# MCU.net
KiCad netlist of a schematic drawn in Altium Designer
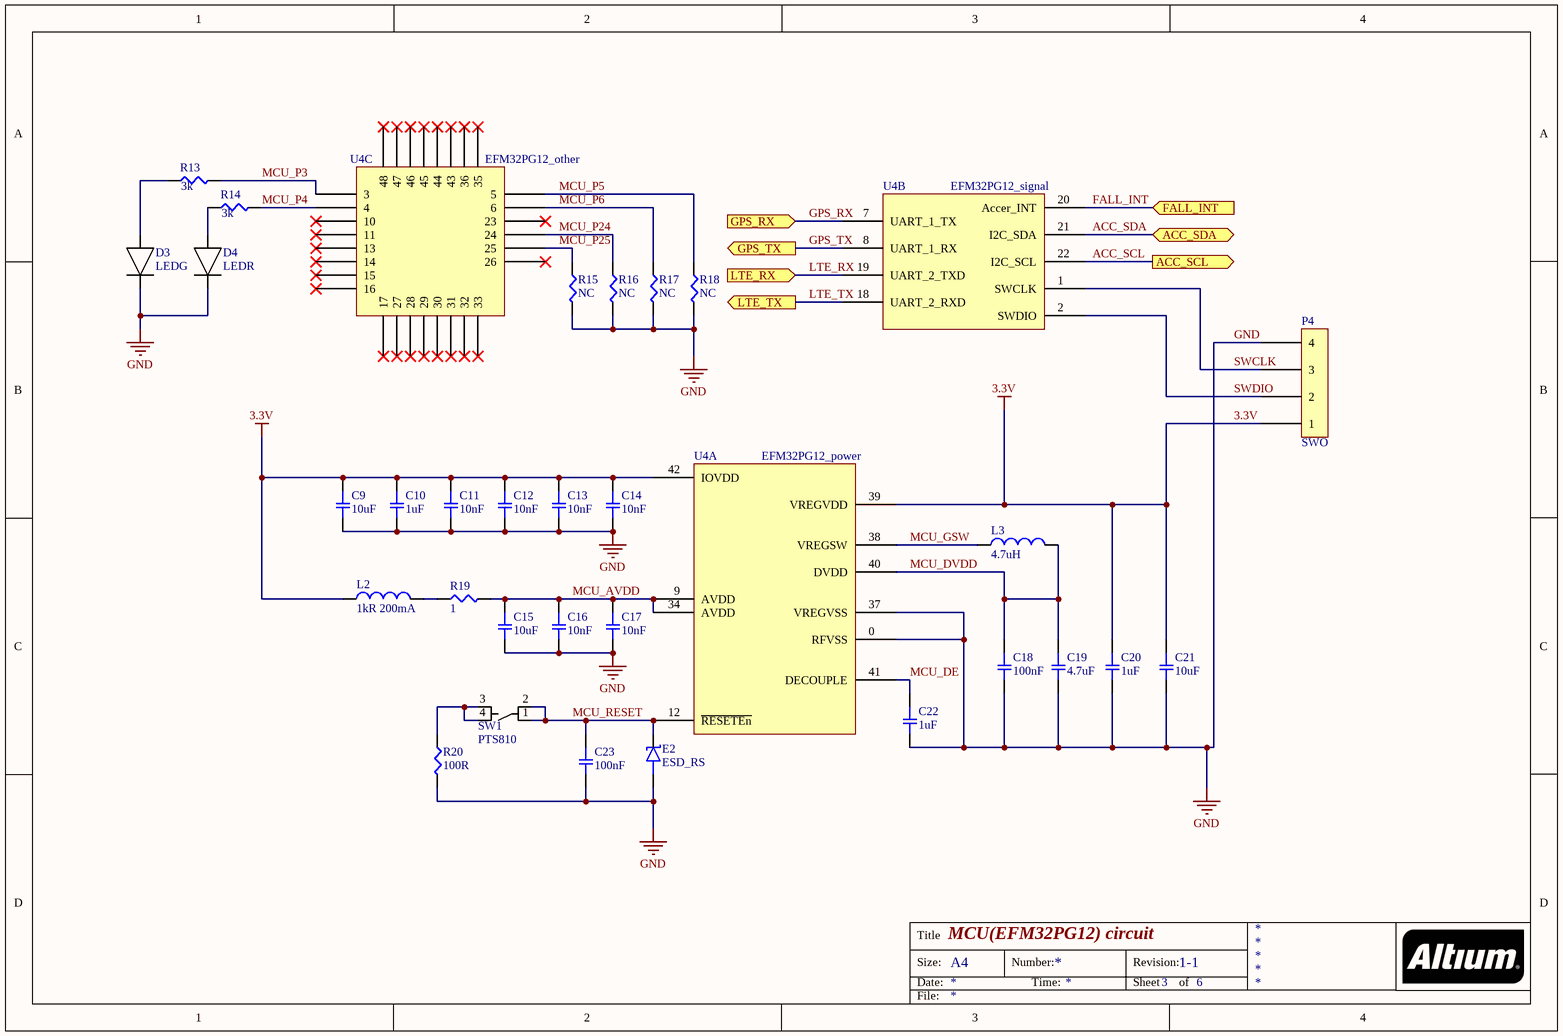
[diagram p0: MCU.SchDoc]

(export (version "E")
  (design (tool "Eeschema 10.0.6"))
  (components
    (comp (ref "C9")
      (value "10uF")
      (footprint "0603-CAP")
      (fields (field (name "Comment") "0603C 10UF"))
      (libsource (lib "passive components") (part "0603C 10UF"))
    )
    (comp (ref "C10")
      (value "1uF")
      (footprint "0603-CAP")
      (fields (field (name "Comment") "0603C 1UF"))
      (libsource (lib "passive components") (part "0603C 1UF"))
    )
    (comp (ref "C11")
      (value "10nF")
      (footprint "0603-CAP")
      (fields (field (name "Comment") "0603C 10NF"))
      (libsource (lib "passive components") (part "0603C 10NF"))
    )
    (comp (ref "C12")
      (value "10nF")
      (footprint "0603-CAP")
      (fields (field (name "Comment") "0603C 10NF"))
      (libsource (lib "passive components") (part "0603C 10NF"))
    )
    (comp (ref "C13")
      (value "10nF")
      (footprint "0603-CAP")
      (fields (field (name "Comment") "0603C 10NF"))
      (libsource (lib "passive components") (part "0603C 10NF"))
    )
    (comp (ref "C14")
      (value "10nF")
      (footprint "0603-CAP")
      (fields (field (name "Comment") "0603C 10NF"))
      (libsource (lib "passive components") (part "0603C 10NF"))
    )
    (comp (ref "C15")
      (value "10uF")
      (footprint "0603-CAP")
      (fields (field (name "Comment") "0603C 10UF"))
      (libsource (lib "passive components") (part "0603C 10UF"))
    )
    (comp (ref "C16")
      (value "10nF")
      (footprint "0603-CAP")
      (fields (field (name "Comment") "0603C 10NF"))
      (libsource (lib "passive components") (part "0603C 10NF"))
    )
    (comp (ref "C17")
      (value "10nF")
      (footprint "0603-CAP")
      (fields (field (name "Comment") "0603C 10NF"))
      (libsource (lib "passive components") (part "0603C 10NF"))
    )
    (comp (ref "C18")
      (value "100nF")
      (footprint "0603-CAP")
      (fields (field (name "Comment") "0603C 100NF"))
      (libsource (lib "passive components") (part "0603C 100NF"))
    )
    (comp (ref "C19")
      (value "4.7uF")
      (footprint "0603-CAP")
      (fields (field (name "Comment") "0603C 4U7F"))
      (libsource (lib "passive components") (part "0603C 4U7F"))
    )
    (comp (ref "C20")
      (value "1uF")
      (footprint "0603-CAP")
      (fields (field (name "Comment") "0603C 1UF"))
      (libsource (lib "passive components") (part "0603C 1UF"))
    )
    (comp (ref "C21")
      (value "10uF")
      (footprint "0603-CAP")
      (fields (field (name "Comment") "0603C 10UF"))
      (libsource (lib "passive components") (part "0603C 10UF"))
    )
    (comp (ref "C22")
      (value "1uF")
      (footprint "0603-CAP")
      (fields (field (name "Comment") "0603C 1UF"))
      (libsource (lib "passive components") (part "0603C 1UF"))
    )
    (comp (ref "C23")
      (value "100nF")
      (footprint "0603-CAP")
      (fields (field (name "Comment") "0603C 100NF"))
      (libsource (lib "passive components") (part "0603C 100NF"))
    )
    (comp (ref "D3")
      (value "LEDG")
      (footprint "0603-LED")
      (libsource (lib "passive components") (part "0603 LEDG"))
    )
    (comp (ref "D4")
      (value "LEDR")
      (footprint "0603-LED")
      (libsource (lib "passive components") (part "0603 LEDR"))
    )
    (comp (ref "E2")
      (value "ESD_RS")
      (footprint "ESD_RS")
      (libsource (lib "passive components") (part "ESD_RESET"))
    )
    (comp (ref "L2")
      (value "1kR 200mA")
      (footprint "0603-FerritBead")
      (fields (field (name "Comment") "Ferrite Bead"))
      (libsource (lib "passive components") (part "Ferrite Bead"))
    )
    (comp (ref "L3")
      (value "4.7uH")
      (footprint "Inductor 4U7H")
      (fields (field (name "Comment") "Inductor 4U7H"))
      (libsource (lib "passive components") (part "Inductor 4U7H"))
    )
    (comp (ref "P4")
      (value "SWO")
      (footprint "4_PINS_2.54")
      (libsource (lib "2.54_Connectors") (part "4pins_connector"))
    )
    (comp (ref "R13")
      (value "3k")
      (footprint "0603-RES")
      (fields (field (name "Comment") "3KR"))
      (libsource (lib "passive components") (part "0603R 3KR"))
    )
    (comp (ref "R14")
      (value "3k")
      (footprint "0603-RES")
      (fields (field (name "Comment") "3KR"))
      (libsource (lib "passive components") (part "0603R 3KR"))
    )
    (comp (ref "R15")
      (value "NC")
      (footprint "0603-RES")
      (fields (field (name "Comment") "0603R NC"))
      (libsource (lib "passive components") (part "0603R NC"))
    )
    (comp (ref "R16")
      (value "NC")
      (footprint "0603-RES")
      (fields (field (name "Comment") "0603R NC"))
      (libsource (lib "passive components") (part "0603R NC"))
    )
    (comp (ref "R17")
      (value "NC")
      (footprint "0603-RES")
      (fields (field (name "Comment") "0603R NC"))
      (libsource (lib "passive components") (part "0603R NC"))
    )
    (comp (ref "R18")
      (value "NC")
      (footprint "0603-RES")
      (fields (field (name "Comment") "0603R NC"))
      (libsource (lib "passive components") (part "0603R NC"))
    )
    (comp (ref "R19")
      (value "1")
      (footprint "0603-RES")
      (fields (field (name "Comment") "0603R 1R"))
      (libsource (lib "passive components") (part "0603R 1R"))
    )
    (comp (ref "R20")
      (value "100R")
      (footprint "0603-RES")
      (fields (field (name "Comment") "0603R 100R"))
      (libsource (lib "passive components") (part "0603R 100R"))
    )
    (comp (ref "SW1")
      (value "PTS810")
      (footprint "PTS810_SJM_250_SMTR_LFS:*SW_PTS810_SJM_250_SMTR_LFS")
      (description "Tactile Switch SPST-NO Top Actuated Surface Mount")
      (fields (field (name "MP") "PTS810 SJM 250 SMTR LFS") (field (name "MF") "C&K"))
      (libsource (lib "PTS810_SJM_250_SMTR_LFS") (part "PTS810_SJM_250_SMTR_LFS"))
    )
    (comp (ref "U4")
      (value "EFM32PG12_power")
      (footprint "QFN50P700X700X90_HS-49N_")
      (fields
        (field (name "MP") "EFM32PG12B500F1024GM48-C")
        (field (name "MF") "Silicon Labs")
        (field (name "DIGIKEY PART NUMBER") "336-4419-ND")
      )
      (libsource (lib "EMF32PG") (part "EFM32PG12"))
    )
  )
  (nets
    (net (code "1") (name "/ACC_SCL") (class "Default")
      (node (ref "U4") (pin "22") (pinfunction "I2C_SCL_22") (pintype "passive"))
    )
    (net (code "2") (name "/ACC_SDA") (class "Default")
      (node (ref "U4") (pin "21") (pinfunction "I2C_SDA_21") (pintype "passive"))
    )
    (net (code "3") (name "/FALL_INT") (class "Default")
      (node (ref "U4") (pin "20") (pinfunction "Accer_INT_20") (pintype "passive"))
    )
    (net (code "4") (name "/GPS_RX") (class "Default")
      (node (ref "U4") (pin "7") (pinfunction "UART_1_TX_7") (pintype "passive"))
    )
    (net (code "5") (name "/GPS_TX") (class "Default")
      (node (ref "U4") (pin "8") (pinfunction "UART_1_RX_8") (pintype "passive"))
    )
    (net (code "6") (name "/LTE_RX") (class "Default")
      (node (ref "U4") (pin "19") (pinfunction "UART_2_TXD_19") (pintype "passive"))
    )
    (net (code "7") (name "/LTE_TX") (class "Default")
      (node (ref "U4") (pin "18") (pinfunction "UART_2_RXD_18") (pintype "passive"))
    )
    (net (code "8") (name "/MCU_AVDD") (class "Default")
      (node (ref "C15") (pin "1") (pinfunction "1_1") (pintype "passive"))
      (node (ref "C16") (pin "1") (pinfunction "1_1") (pintype "passive"))
      (node (ref "C17") (pin "1") (pinfunction "1_1") (pintype "passive"))
      (node (ref "R19") (pin "2") (pinfunction "2_2") (pintype "passive"))
      (node (ref "U4") (pin "34") (pinfunction "AVDD_34") (pintype "passive"))
      (node (ref "U4") (pin "9") (pinfunction "AVDD_9") (pintype "passive"))
    )
    (net (code "9") (name "/MCU_DE") (class "Default")
      (node (ref "C22") (pin "1") (pinfunction "1_1") (pintype "passive"))
      (node (ref "U4") (pin "41") (pinfunction "DECOUPLE_41") (pintype "passive"))
    )
    (net (code "10") (name "/MCU_DVDD") (class "Default")
      (node (ref "C18") (pin "1") (pinfunction "1_1") (pintype "passive"))
      (node (ref "C19") (pin "1") (pinfunction "1_1") (pintype "passive"))
      (node (ref "L3") (pin "2") (pinfunction "2_2") (pintype "passive"))
      (node (ref "U4") (pin "40") (pinfunction "DVDD_40") (pintype "passive"))
    )
    (net (code "11") (name "/MCU_GSW") (class "Default")
      (node (ref "L3") (pin "1") (pinfunction "1_1") (pintype "passive"))
      (node (ref "U4") (pin "38") (pinfunction "VREGSW_38") (pintype "passive"))
    )
    (net (code "12") (name "/MCU_P3") (class "Default")
      (node (ref "R13") (pin "2") (pinfunction "2_2") (pintype "passive"))
      (node (ref "U4") (pin "3") (pinfunction "3_3") (pintype "passive"))
    )
    (net (code "13") (name "/MCU_P4") (class "Default")
      (node (ref "R14") (pin "2") (pinfunction "2_2") (pintype "passive"))
      (node (ref "U4") (pin "4") (pinfunction "4_4") (pintype "passive"))
    )
    (net (code "14") (name "/MCU_P5") (class "Default")
      (node (ref "R18") (pin "1") (pinfunction "1_1") (pintype "passive"))
      (node (ref "U4") (pin "5") (pinfunction "5_5") (pintype "passive"))
    )
    (net (code "15") (name "/MCU_P6") (class "Default")
      (node (ref "R17") (pin "1") (pinfunction "1_1") (pintype "passive"))
      (node (ref "U4") (pin "6") (pinfunction "6_6") (pintype "passive"))
    )
    (net (code "16") (name "/MCU_P24") (class "Default")
      (node (ref "R16") (pin "1") (pinfunction "1_1") (pintype "passive"))
      (node (ref "U4") (pin "24") (pinfunction "24_24") (pintype "passive"))
    )
    (net (code "17") (name "/MCU_P25") (class "Default")
      (node (ref "R15") (pin "1") (pinfunction "1_1") (pintype "passive"))
      (node (ref "U4") (pin "25") (pinfunction "25_25") (pintype "passive"))
    )
    (net (code "18") (name "/MCU_RESET") (class "Default")
      (node (ref "C23") (pin "1") (pinfunction "1_1") (pintype "passive"))
      (node (ref "E2") (pin "1") (pinfunction "1_1") (pintype "passive"))
      (node (ref "SW1") (pin "1") (pinfunction "1_1") (pintype "passive"))
      (node (ref "SW1") (pin "2") (pinfunction "2_2") (pintype "passive"))
      (node (ref "U4") (pin "12") (pinfunction "~{RESETEn}_12") (pintype "passive"))
    )
    (net (code "19") (name "/SWCLK") (class "Default")
      (node (ref "P4") (pin "3") (pinfunction "3_3") (pintype "passive"))
      (node (ref "U4") (pin "1") (pinfunction "SWCLK_1") (pintype "passive"))
    )
    (net (code "20") (name "/SWDIO") (class "Default")
      (node (ref "P4") (pin "2") (pinfunction "2_2") (pintype "passive"))
      (node (ref "U4") (pin "2") (pinfunction "SWDIO_2") (pintype "passive"))
    )
    (net (code "21") (name "3.3V") (class "Default")
      (node (ref "C10") (pin "1") (pinfunction "1_1") (pintype "passive"))
      (node (ref "C11") (pin "1") (pinfunction "1_1") (pintype "passive"))
      (node (ref "C12") (pin "1") (pinfunction "1_1") (pintype "passive"))
      (node (ref "C13") (pin "1") (pinfunction "1_1") (pintype "passive"))
      (node (ref "C14") (pin "1") (pinfunction "1_1") (pintype "passive"))
      (node (ref "C20") (pin "1") (pinfunction "1_1") (pintype "passive"))
      (node (ref "C21") (pin "1") (pinfunction "1_1") (pintype "passive"))
      (node (ref "C9") (pin "1") (pinfunction "1_1") (pintype "passive"))
      (node (ref "L2") (pin "1") (pinfunction "1_1") (pintype "passive"))
      (node (ref "P4") (pin "1") (pinfunction "1_1") (pintype "passive"))
      (node (ref "U4") (pin "39") (pinfunction "VREGVDD_39") (pintype "passive"))
      (node (ref "U4") (pin "42") (pinfunction "IOVDD_42") (pintype "passive"))
    )
    (net (code "22") (name "GND") (class "Default")
      (node (ref "C10") (pin "2") (pinfunction "2_2") (pintype "passive"))
      (node (ref "C11") (pin "2") (pinfunction "2_2") (pintype "passive"))
      (node (ref "C12") (pin "2") (pinfunction "2_2") (pintype "passive"))
      (node (ref "C13") (pin "2") (pinfunction "2_2") (pintype "passive"))
      (node (ref "C14") (pin "2") (pinfunction "2_2") (pintype "passive"))
      (node (ref "C15") (pin "2") (pinfunction "2_2") (pintype "passive"))
      (node (ref "C16") (pin "2") (pinfunction "2_2") (pintype "passive"))
      (node (ref "C17") (pin "2") (pinfunction "2_2") (pintype "passive"))
      (node (ref "C18") (pin "2") (pinfunction "2_2") (pintype "passive"))
      (node (ref "C19") (pin "2") (pinfunction "2_2") (pintype "passive"))
      (node (ref "C20") (pin "2") (pinfunction "2_2") (pintype "passive"))
      (node (ref "C21") (pin "2") (pinfunction "2_2") (pintype "passive"))
      (node (ref "C22") (pin "2") (pinfunction "2_2") (pintype "passive"))
      (node (ref "C23") (pin "2") (pinfunction "2_2") (pintype "passive"))
      (node (ref "C9") (pin "2") (pinfunction "2_2") (pintype "passive"))
      (node (ref "D3") (pin "2") (pinfunction "2_2") (pintype "passive"))
      (node (ref "D4") (pin "2") (pinfunction "2_2") (pintype "passive"))
      (node (ref "E2") (pin "2") (pinfunction "2_2") (pintype "passive"))
      (node (ref "P4") (pin "4") (pinfunction "4_4") (pintype "passive"))
      (node (ref "R15") (pin "2") (pinfunction "2_2") (pintype "passive"))
      (node (ref "R16") (pin "2") (pinfunction "2_2") (pintype "passive"))
      (node (ref "R17") (pin "2") (pinfunction "2_2") (pintype "passive"))
      (node (ref "R18") (pin "2") (pinfunction "2_2") (pintype "passive"))
      (node (ref "R20") (pin "2") (pinfunction "2_2") (pintype "passive"))
      (node (ref "U4") (pin "0") (pinfunction "RFVSS_0") (pintype "passive"))
      (node (ref "U4") (pin "37") (pinfunction "VREGVSS_37") (pintype "passive"))
    )
    (net (code "23") (name "Net-(D3-Pad1)") (class "Default")
      (node (ref "D3") (pin "1") (pinfunction "1_1") (pintype "passive"))
      (node (ref "R13") (pin "1") (pinfunction "1_1") (pintype "passive"))
    )
    (net (code "24") (name "Net-(D4-Pad1)") (class "Default")
      (node (ref "D4") (pin "1") (pinfunction "1_1") (pintype "passive"))
      (node (ref "R14") (pin "1") (pinfunction "1_1") (pintype "passive"))
    )
    (net (code "25") (name "Net-(L2-Pad2)") (class "Default")
      (node (ref "L2") (pin "2") (pinfunction "2_2") (pintype "passive"))
      (node (ref "R19") (pin "1") (pinfunction "1_1") (pintype "passive"))
    )
    (net (code "26") (name "Net-(R20-Pad1)") (class "Default")
      (node (ref "R20") (pin "1") (pinfunction "1_1") (pintype "passive"))
      (node (ref "SW1") (pin "3") (pinfunction "3_3") (pintype "passive"))
      (node (ref "SW1") (pin "4") (pinfunction "4_4") (pintype "passive"))
    )
    (net (code "27") (name "unconnected-(U4-Pad10)") (class "Default")
      (node (ref "U4") (pin "10") (pinfunction "10_10") (pintype "passive+no_connect"))
    )
    (net (code "28") (name "unconnected-(U4-Pad11)") (class "Default")
      (node (ref "U4") (pin "11") (pinfunction "11_11") (pintype "passive+no_connect"))
    )
    (net (code "29") (name "unconnected-(U4-Pad13)") (class "Default")
      (node (ref "U4") (pin "13") (pinfunction "13_13") (pintype "passive+no_connect"))
    )
    (net (code "30") (name "unconnected-(U4-Pad14)") (class "Default")
      (node (ref "U4") (pin "14") (pinfunction "14_14") (pintype "passive+no_connect"))
    )
    (net (code "31") (name "unconnected-(U4-Pad15)") (class "Default")
      (node (ref "U4") (pin "15") (pinfunction "15_15") (pintype "passive+no_connect"))
    )
    (net (code "32") (name "unconnected-(U4-Pad16)") (class "Default")
      (node (ref "U4") (pin "16") (pinfunction "16_16") (pintype "passive+no_connect"))
    )
    (net (code "33") (name "unconnected-(U4-Pad17)") (class "Default")
      (node (ref "U4") (pin "17") (pinfunction "17_17") (pintype "passive+no_connect"))
    )
    (net (code "34") (name "unconnected-(U4-Pad23)") (class "Default")
      (node (ref "U4") (pin "23") (pinfunction "23_23") (pintype "passive+no_connect"))
    )
    (net (code "35") (name "unconnected-(U4-Pad26)") (class "Default")
      (node (ref "U4") (pin "26") (pinfunction "26_26") (pintype "passive+no_connect"))
    )
    (net (code "36") (name "unconnected-(U4-Pad27)") (class "Default")
      (node (ref "U4") (pin "27") (pinfunction "27_27") (pintype "passive+no_connect"))
    )
    (net (code "37") (name "unconnected-(U4-Pad28)") (class "Default")
      (node (ref "U4") (pin "28") (pinfunction "28_28") (pintype "passive+no_connect"))
    )
    (net (code "38") (name "unconnected-(U4-Pad29)") (class "Default")
      (node (ref "U4") (pin "29") (pinfunction "29_29") (pintype "passive+no_connect"))
    )
    (net (code "39") (name "unconnected-(U4-Pad30)") (class "Default")
      (node (ref "U4") (pin "30") (pinfunction "30_30") (pintype "passive+no_connect"))
    )
    (net (code "40") (name "unconnected-(U4-Pad31)") (class "Default")
      (node (ref "U4") (pin "31") (pinfunction "31_31") (pintype "passive+no_connect"))
    )
    (net (code "41") (name "unconnected-(U4-Pad32)") (class "Default")
      (node (ref "U4") (pin "32") (pinfunction "32_32") (pintype "passive+no_connect"))
    )
    (net (code "42") (name "unconnected-(U4-Pad33)") (class "Default")
      (node (ref "U4") (pin "33") (pinfunction "33_33") (pintype "passive+no_connect"))
    )
    (net (code "43") (name "unconnected-(U4-Pad35)") (class "Default")
      (node (ref "U4") (pin "35") (pinfunction "35_35") (pintype "passive+no_connect"))
    )
    (net (code "44") (name "unconnected-(U4-Pad36)") (class "Default")
      (node (ref "U4") (pin "36") (pinfunction "36_36") (pintype "passive+no_connect"))
    )
    (net (code "45") (name "unconnected-(U4-Pad43)") (class "Default")
      (node (ref "U4") (pin "43") (pinfunction "43_43") (pintype "passive+no_connect"))
    )
    (net (code "46") (name "unconnected-(U4-Pad44)") (class "Default")
      (node (ref "U4") (pin "44") (pinfunction "44_44") (pintype "passive+no_connect"))
    )
    (net (code "47") (name "unconnected-(U4-Pad45)") (class "Default")
      (node (ref "U4") (pin "45") (pinfunction "45_45") (pintype "passive+no_connect"))
    )
    (net (code "48") (name "unconnected-(U4-Pad46)") (class "Default")
      (node (ref "U4") (pin "46") (pinfunction "46_46") (pintype "passive+no_connect"))
    )
    (net (code "49") (name "unconnected-(U4-Pad47)") (class "Default")
      (node (ref "U4") (pin "47") (pinfunction "47_47") (pintype "passive+no_connect"))
    )
    (net (code "50") (name "unconnected-(U4-Pad48)") (class "Default")
      (node (ref "U4") (pin "48") (pinfunction "48_48") (pintype "passive+no_connect"))
    )
  )
)
